# RAM.net
KiCad netlist of a schematic drawn in Altium Designer
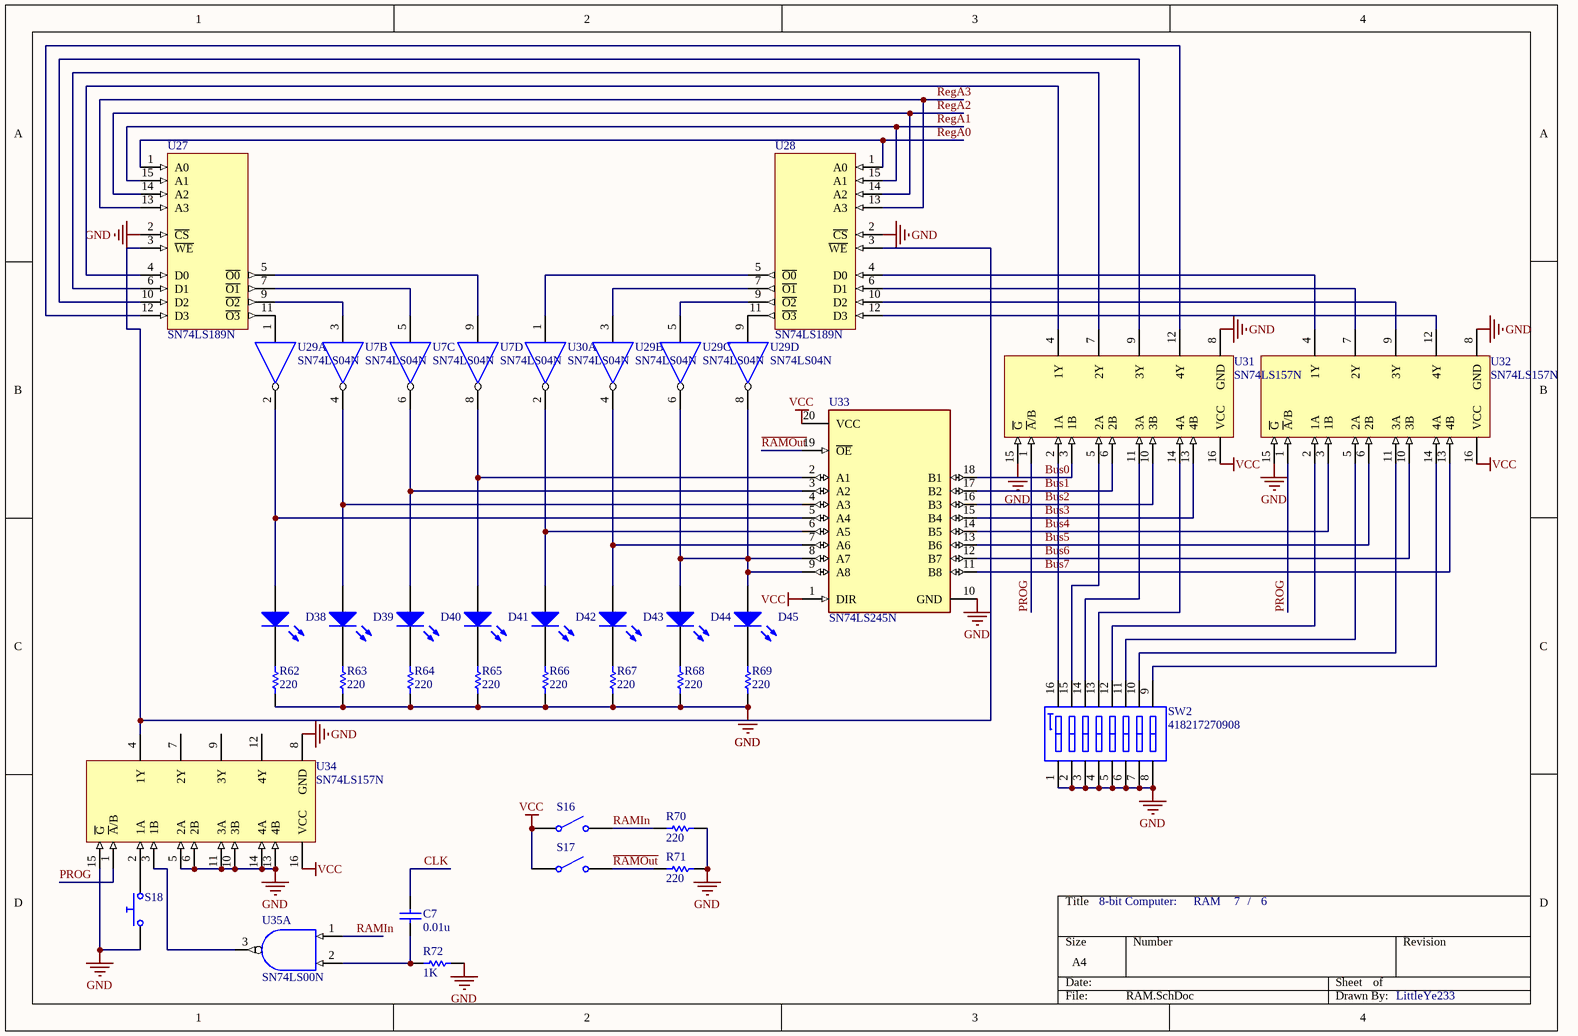
[diagram p0: RAM.SchDoc]

(export (version "E")
  (design (tool "Eeschema 10.0.6"))
  (components
    (comp (ref "C7")
      (value "0.01u")
      (description "Capacitor")
      (libsource (lib "Simulation Generic Components") (part "Capacitor"))
    )
    (comp (ref "D38")
      (value "Light-Emitting Diode")
      (libsource (lib "Simulation Generic Components") (part "LED"))
    )
    (comp (ref "D39")
      (value "Light-Emitting Diode")
      (libsource (lib "Simulation Generic Components") (part "LED"))
    )
    (comp (ref "D40")
      (value "Light-Emitting Diode")
      (libsource (lib "Simulation Generic Components") (part "LED"))
    )
    (comp (ref "D41")
      (value "Light-Emitting Diode")
      (libsource (lib "Simulation Generic Components") (part "LED"))
    )
    (comp (ref "D42")
      (value "Light-Emitting Diode")
      (libsource (lib "Simulation Generic Components") (part "LED"))
    )
    (comp (ref "D43")
      (value "Light-Emitting Diode")
      (libsource (lib "Simulation Generic Components") (part "LED"))
    )
    (comp (ref "D44")
      (value "Light-Emitting Diode")
      (libsource (lib "Simulation Generic Components") (part "LED"))
    )
    (comp (ref "D45")
      (value "Light-Emitting Diode")
      (libsource (lib "Simulation Generic Components") (part "LED"))
    )
    (comp (ref "R62")
      (value "220")
      (description "Resistor")
      (libsource (lib "Simulation Generic Components") (part "Resistor"))
    )
    (comp (ref "R63")
      (value "220")
      (description "Resistor")
      (libsource (lib "Simulation Generic Components") (part "Resistor"))
    )
    (comp (ref "R64")
      (value "220")
      (description "Resistor")
      (libsource (lib "Simulation Generic Components") (part "Resistor"))
    )
    (comp (ref "R65")
      (value "220")
      (description "Resistor")
      (libsource (lib "Simulation Generic Components") (part "Resistor"))
    )
    (comp (ref "R66")
      (value "220")
      (description "Resistor")
      (libsource (lib "Simulation Generic Components") (part "Resistor"))
    )
    (comp (ref "R67")
      (value "220")
      (description "Resistor")
      (libsource (lib "Simulation Generic Components") (part "Resistor"))
    )
    (comp (ref "R68")
      (value "220")
      (description "Resistor")
      (libsource (lib "Simulation Generic Components") (part "Resistor"))
    )
    (comp (ref "R69")
      (value "220")
      (description "Resistor")
      (libsource (lib "Simulation Generic Components") (part "Resistor"))
    )
    (comp (ref "R70")
      (value "220")
      (description "Resistor")
      (libsource (lib "Simulation Generic Components") (part "Resistor"))
    )
    (comp (ref "R71")
      (value "220")
      (description "Resistor")
      (libsource (lib "Simulation Generic Components") (part "Resistor"))
    )
    (comp (ref "R72")
      (value "1K")
      (description "Resistor")
      (libsource (lib "Simulation Generic Components") (part "Resistor"))
    )
    (comp (ref "S16")
      (value "Single-Pole, Single-Throw Switch")
      (libsource (lib "Simulation Generic Components") (part "SPST SW"))
    )
    (comp (ref "S17")
      (value "Single-Pole, Single-Throw Switch")
      (libsource (lib "Simulation Generic Components") (part "SPST SW"))
    )
    (comp (ref "S18")
      (value "Push Button Normally Opened")
      (libsource (lib "Simulation Generic Components") (part "Push Button NO"))
    )
    (comp (ref "SW2")
      (value "418217270908")
      (footprint "418217270908")
      (description "WS-DITU 2.54 mm right angled compact THT Dip Switch with raised actuator")
      (fields (field (name "MANUFACTURER") "Wuerth Elektronik"))
      (libsource (lib "418217270908") (part "CMP-1441-00017-1"))
    )
    (comp (ref "U7")
      (value "SN74LS04N")
      (footprint "N0014A")
      (description "Hex inverters, N0014A, TUBE")
      (fields
        (field (name "MANUFACTURER") "Texas Instruments")
        (field (name "GENERIC PART NUMBER") "SN74LS04")
      )
      (libsource (lib "SN74LS04N") (part "CMP-1615-00911-2"))
    )
    (comp (ref "U27") (value "SN74LS189N") (libsource (lib "SN74LS189N") (part "SN74LS189N")))
    (comp (ref "U28") (value "SN74LS189N") (libsource (lib "") (part "SN74LS189N_1")))
    (comp (ref "U29")
      (value "SN74LS04N")
      (footprint "N0014A")
      (description "Hex inverters, N0014A, TUBE")
      (fields
        (field (name "MANUFACTURER") "Texas Instruments")
        (field (name "GENERIC PART NUMBER") "SN74LS04")
      )
      (libsource (lib "SN74LS04N") (part "CMP-1615-00911-2"))
    )
    (comp (ref "U30")
      (value "SN74LS04N")
      (footprint "N0014A")
      (description "Hex inverters, N0014A, TUBE")
      (fields
        (field (name "MANUFACTURER") "Texas Instruments")
        (field (name "GENERIC PART NUMBER") "SN74LS04")
      )
      (libsource (lib "SN74LS04N") (part "CMP-1615-00911-2"))
    )
    (comp (ref "U31")
      (value "SN74LS157N")
      (footprint "N0016A")
      (description "Quadruple 2-Line To 1-Line Data Selectors/Multiplexers, N0016A, TUBE")
      (fields
        (field (name "MANUFACTURER") "Texas Instruments")
        (field (name "GENERIC PART NUMBER") "SN74LS157")
      )
      (libsource (lib "SN74LS157N") (part "CMP-1633-00683-2"))
    )
    (comp (ref "U32")
      (value "SN74LS157N")
      (footprint "N0016A")
      (description "Quadruple 2-Line To 1-Line Data Selectors/Multiplexers, N0016A, TUBE")
      (fields
        (field (name "MANUFACTURER") "Texas Instruments")
        (field (name "GENERIC PART NUMBER") "SN74LS157")
      )
      (libsource (lib "SN74LS157N") (part "CMP-1633-00683-2"))
    )
    (comp (ref "U33")
      (value "SN74LS245N")
      (footprint "FP-N0020A-MFG")
      (description "IC TXRX NON-INVERT 5.25V 20DIP")
      (libsource (lib "SN74LS245N") (part "CMP-1620-00419-3"))
    )
    (comp (ref "U34")
      (value "SN74LS157N")
      (footprint "N0016A")
      (description "Quadruple 2-Line To 1-Line Data Selectors/Multiplexers, N0016A, TUBE")
      (fields
        (field (name "MANUFACTURER") "Texas Instruments")
        (field (name "GENERIC PART NUMBER") "SN74LS157")
      )
      (libsource (lib "SN74LS157N") (part "CMP-1633-00683-2"))
    )
    (comp (ref "U35")
      (value "SN74LS00N")
      (footprint "N0014A")
      (description "Quad 2-input positive-NAND gates, N0014A, TUBE")
      (fields
        (field (name "MANUFACTURER") "Texas Instruments")
        (field (name "GENERIC PART NUMBER") "SN74LS00")
      )
      (libsource (lib "SN74LS00N") (part "CMP-1627-00476-2"))
    )
  )
  (nets
    (net (code "1") (name "/Bus0") (class "Default")
      (node (ref "U31") (pin "3") (pinfunction "1B_3") (pintype "input"))
      (node (ref "U33") (pin "18") (pinfunction "B1_18") (pintype "bidirectional"))
    )
    (net (code "2") (name "/Bus1") (class "Default")
      (node (ref "U31") (pin "6") (pinfunction "2B_6") (pintype "input"))
      (node (ref "U33") (pin "17") (pinfunction "B2_17") (pintype "bidirectional"))
    )
    (net (code "3") (name "/Bus2") (class "Default")
      (node (ref "U31") (pin "10") (pinfunction "3B_10") (pintype "input"))
      (node (ref "U33") (pin "16") (pinfunction "B3_16") (pintype "bidirectional"))
    )
    (net (code "4") (name "/Bus3") (class "Default")
      (node (ref "U31") (pin "13") (pinfunction "4B_13") (pintype "input"))
      (node (ref "U33") (pin "15") (pinfunction "B4_15") (pintype "bidirectional"))
    )
    (net (code "5") (name "/Bus4") (class "Default")
      (node (ref "U32") (pin "3") (pinfunction "1B_3") (pintype "input"))
      (node (ref "U33") (pin "14") (pinfunction "B5_14") (pintype "bidirectional"))
    )
    (net (code "6") (name "/Bus5") (class "Default")
      (node (ref "U32") (pin "6") (pinfunction "2B_6") (pintype "input"))
      (node (ref "U33") (pin "13") (pinfunction "B6_13") (pintype "bidirectional"))
    )
    (net (code "7") (name "/Bus6") (class "Default")
      (node (ref "U32") (pin "10") (pinfunction "3B_10") (pintype "input"))
      (node (ref "U33") (pin "12") (pinfunction "B7_12") (pintype "bidirectional"))
    )
    (net (code "8") (name "/Bus7") (class "Default")
      (node (ref "U32") (pin "13") (pinfunction "4B_13") (pintype "input"))
      (node (ref "U33") (pin "11") (pinfunction "B8_11") (pintype "bidirectional"))
    )
    (net (code "9") (name "/CLK") (class "Default")
      (node (ref "C7") (pin "2") (pinfunction "2_2") (pintype "passive"))
    )
    (net (code "10") (name "/PROG") (class "Default")
      (node (ref "U31") (pin "1") (pinfunction "~{A}/B_1") (pintype "input"))
      (node (ref "U32") (pin "1") (pinfunction "~{A}/B_1") (pintype "input"))
      (node (ref "U34") (pin "1") (pinfunction "~{A}/B_1") (pintype "input"))
    )
    (net (code "11") (name "/RAMIn") (class "Default")
      (node (ref "R70") (pin "2") (pinfunction "2_2") (pintype "passive"))
      (node (ref "S16") (pin "2") (pinfunction "2_2") (pintype "passive"))
      (node (ref "U35") (pin "1") (pinfunction "1A_1") (pintype "input"))
    )
    (net (code "12") (name "/RegA0") (class "Default")
      (node (ref "U27") (pin "1") (pinfunction "A0_1") (pintype "input"))
      (node (ref "U28") (pin "1") (pinfunction "A0_1") (pintype "input"))
    )
    (net (code "13") (name "/RegA1") (class "Default")
      (node (ref "U27") (pin "15") (pinfunction "A1_15") (pintype "input"))
      (node (ref "U28") (pin "15") (pinfunction "A1_15") (pintype "input"))
    )
    (net (code "14") (name "/RegA2") (class "Default")
      (node (ref "U27") (pin "14") (pinfunction "A2_14") (pintype "input"))
      (node (ref "U28") (pin "14") (pinfunction "A2_14") (pintype "input"))
    )
    (net (code "15") (name "/RegA3") (class "Default")
      (node (ref "U27") (pin "13") (pinfunction "A3_13") (pintype "input"))
      (node (ref "U28") (pin "13") (pinfunction "A3_13") (pintype "input"))
    )
    (net (code "16") (name "/~{RAMOut}") (class "Default")
      (node (ref "R71") (pin "2") (pinfunction "2_2") (pintype "passive"))
      (node (ref "S17") (pin "2") (pinfunction "2_2") (pintype "passive"))
      (node (ref "U33") (pin "19") (pinfunction "~{OE}_19") (pintype "input"))
    )
    (net (code "17") (name "GND") (class "Default")
      (node (ref "R62") (pin "1") (pinfunction "1_1") (pintype "passive"))
      (node (ref "R63") (pin "1") (pinfunction "1_1") (pintype "passive"))
      (node (ref "R64") (pin "1") (pinfunction "1_1") (pintype "passive"))
      (node (ref "R65") (pin "1") (pinfunction "1_1") (pintype "passive"))
      (node (ref "R66") (pin "1") (pinfunction "1_1") (pintype "passive"))
      (node (ref "R67") (pin "1") (pinfunction "1_1") (pintype "passive"))
      (node (ref "R68") (pin "1") (pinfunction "1_1") (pintype "passive"))
      (node (ref "R69") (pin "1") (pinfunction "1_1") (pintype "passive"))
      (node (ref "R70") (pin "1") (pinfunction "1_1") (pintype "passive"))
      (node (ref "R71") (pin "1") (pinfunction "1_1") (pintype "passive"))
      (node (ref "R72") (pin "2") (pinfunction "2_2") (pintype "passive"))
      (node (ref "S18") (pin "1") (pinfunction "1_1") (pintype "passive"))
      (node (ref "SW2") (pin "1") (pinfunction "1_1") (pintype "passive"))
      (node (ref "SW2") (pin "2") (pinfunction "2_2") (pintype "passive"))
      (node (ref "SW2") (pin "3") (pinfunction "3_3") (pintype "passive"))
      (node (ref "SW2") (pin "4") (pinfunction "4_4") (pintype "passive"))
      (node (ref "SW2") (pin "5") (pinfunction "5_5") (pintype "passive"))
      (node (ref "SW2") (pin "6") (pinfunction "6_6") (pintype "passive"))
      (node (ref "SW2") (pin "7") (pinfunction "7_7") (pintype "passive"))
      (node (ref "SW2") (pin "8") (pinfunction "8_8") (pintype "passive"))
      (node (ref "U27") (pin "2") (pinfunction "~{CS}_2") (pintype "input"))
      (node (ref "U28") (pin "2") (pinfunction "~{CS}_2") (pintype "input"))
      (node (ref "U31") (pin "15") (pinfunction "~{G}_15") (pintype "input"))
      (node (ref "U31") (pin "8") (pinfunction "GND_8") (pintype "power_in"))
      (node (ref "U32") (pin "15") (pinfunction "~{G}_15") (pintype "input"))
      (node (ref "U32") (pin "8") (pinfunction "GND_8") (pintype "power_in"))
      (node (ref "U33") (pin "10") (pinfunction "GND_10") (pintype "power_in"))
      (node (ref "U34") (pin "10") (pinfunction "3B_10") (pintype "input"))
      (node (ref "U34") (pin "11") (pinfunction "3A_11") (pintype "input"))
      (node (ref "U34") (pin "13") (pinfunction "4B_13") (pintype "input"))
      (node (ref "U34") (pin "14") (pinfunction "4A_14") (pintype "input"))
      (node (ref "U34") (pin "15") (pinfunction "~{G}_15") (pintype "input"))
      (node (ref "U34") (pin "5") (pinfunction "2A_5") (pintype "input"))
      (node (ref "U34") (pin "6") (pinfunction "2B_6") (pintype "input"))
      (node (ref "U34") (pin "8") (pinfunction "GND_8") (pintype "power_in"))
    )
    (net (code "18") (name "Net-(D38-A)") (class "Default")
      (node (ref "D38") (pin "1") (pinfunction "A_1") (pintype "passive"))
      (node (ref "U29") (pin "2") (pinfunction "~{1Y}_2") (pintype "passive"))
      (node (ref "U33") (pin "5") (pinfunction "A4_5") (pintype "bidirectional"))
    )
    (net (code "19") (name "Net-(D38-K)") (class "Default")
      (node (ref "D38") (pin "2") (pinfunction "K_2") (pintype "passive"))
      (node (ref "R62") (pin "2") (pinfunction "2_2") (pintype "passive"))
    )
    (net (code "20") (name "Net-(D39-A)") (class "Default")
      (node (ref "D39") (pin "1") (pinfunction "A_1") (pintype "passive"))
      (node (ref "U33") (pin "4") (pinfunction "A3_4") (pintype "bidirectional"))
      (node (ref "U7") (pin "4") (pinfunction "~{2Y}_4") (pintype "passive"))
    )
    (net (code "21") (name "Net-(D39-K)") (class "Default")
      (node (ref "D39") (pin "2") (pinfunction "K_2") (pintype "passive"))
      (node (ref "R63") (pin "2") (pinfunction "2_2") (pintype "passive"))
    )
    (net (code "22") (name "Net-(D40-A)") (class "Default")
      (node (ref "D40") (pin "1") (pinfunction "A_1") (pintype "passive"))
      (node (ref "U33") (pin "3") (pinfunction "A2_3") (pintype "bidirectional"))
      (node (ref "U7") (pin "6") (pinfunction "~{3Y}_6") (pintype "passive"))
    )
    (net (code "23") (name "Net-(D40-K)") (class "Default")
      (node (ref "D40") (pin "2") (pinfunction "K_2") (pintype "passive"))
      (node (ref "R64") (pin "2") (pinfunction "2_2") (pintype "passive"))
    )
    (net (code "24") (name "Net-(D41-A)") (class "Default")
      (node (ref "D41") (pin "1") (pinfunction "A_1") (pintype "passive"))
      (node (ref "U33") (pin "2") (pinfunction "A1_2") (pintype "bidirectional"))
      (node (ref "U7") (pin "8") (pinfunction "~{4Y}_8") (pintype "passive"))
    )
    (net (code "25") (name "Net-(D41-K)") (class "Default")
      (node (ref "D41") (pin "2") (pinfunction "K_2") (pintype "passive"))
      (node (ref "R65") (pin "2") (pinfunction "2_2") (pintype "passive"))
    )
    (net (code "26") (name "Net-(D42-A)") (class "Default")
      (node (ref "D42") (pin "1") (pinfunction "A_1") (pintype "passive"))
      (node (ref "U30") (pin "2") (pinfunction "~{1Y}_2") (pintype "passive"))
      (node (ref "U33") (pin "6") (pinfunction "A5_6") (pintype "bidirectional"))
    )
    (net (code "27") (name "Net-(D42-K)") (class "Default")
      (node (ref "D42") (pin "2") (pinfunction "K_2") (pintype "passive"))
      (node (ref "R66") (pin "2") (pinfunction "2_2") (pintype "passive"))
    )
    (net (code "28") (name "Net-(D43-A)") (class "Default")
      (node (ref "D43") (pin "1") (pinfunction "A_1") (pintype "passive"))
      (node (ref "U29") (pin "4") (pinfunction "~{2Y}_4") (pintype "passive"))
      (node (ref "U33") (pin "7") (pinfunction "A6_7") (pintype "bidirectional"))
    )
    (net (code "29") (name "Net-(D43-K)") (class "Default")
      (node (ref "D43") (pin "2") (pinfunction "K_2") (pintype "passive"))
      (node (ref "R67") (pin "2") (pinfunction "2_2") (pintype "passive"))
    )
    (net (code "30") (name "Net-(D44-A)") (class "Default")
      (node (ref "D44") (pin "1") (pinfunction "A_1") (pintype "passive"))
      (node (ref "D45") (pin "1") (pinfunction "A_1") (pintype "passive"))
      (node (ref "U29") (pin "6") (pinfunction "~{3Y}_6") (pintype "passive"))
      (node (ref "U29") (pin "8") (pinfunction "~{4Y}_8") (pintype "passive"))
      (node (ref "U33") (pin "8") (pinfunction "A7_8") (pintype "bidirectional"))
      (node (ref "U33") (pin "9") (pinfunction "A8_9") (pintype "bidirectional"))
    )
    (net (code "31") (name "Net-(D44-K)") (class "Default")
      (node (ref "D44") (pin "2") (pinfunction "K_2") (pintype "passive"))
      (node (ref "R68") (pin "2") (pinfunction "2_2") (pintype "passive"))
    )
    (net (code "32") (name "Net-(D45-K)") (class "Default")
      (node (ref "D45") (pin "2") (pinfunction "K_2") (pintype "passive"))
      (node (ref "R69") (pin "2") (pinfunction "2_2") (pintype "passive"))
    )
    (net (code "33") (name "Net-(U27-D0)") (class "Default")
      (node (ref "U27") (pin "4") (pinfunction "D0_4") (pintype "input"))
      (node (ref "U31") (pin "4") (pinfunction "1Y_4") (pintype "passive"))
    )
    (net (code "34") (name "Net-(U27-D1)") (class "Default")
      (node (ref "U27") (pin "6") (pinfunction "D1_6") (pintype "input"))
      (node (ref "U31") (pin "7") (pinfunction "2Y_7") (pintype "passive"))
    )
    (net (code "35") (name "Net-(U27-D2)") (class "Default")
      (node (ref "U27") (pin "10") (pinfunction "D2_10") (pintype "input"))
      (node (ref "U31") (pin "9") (pinfunction "3Y_9") (pintype "passive"))
    )
    (net (code "36") (name "Net-(U27-D3)") (class "Default")
      (node (ref "U27") (pin "12") (pinfunction "D3_12") (pintype "input"))
      (node (ref "U31") (pin "12") (pinfunction "4Y_12") (pintype "passive"))
    )
    (net (code "37") (name "Net-(U27-~{O0})") (class "Default")
      (node (ref "U27") (pin "5") (pinfunction "~{O0}_5") (pintype "output"))
      (node (ref "U7") (pin "9") (pinfunction "4A_9") (pintype "passive"))
    )
    (net (code "38") (name "Net-(U27-~{O1})") (class "Default")
      (node (ref "U27") (pin "7") (pinfunction "~{O1}_7") (pintype "output"))
      (node (ref "U7") (pin "5") (pinfunction "3A_5") (pintype "passive"))
    )
    (net (code "39") (name "Net-(U27-~{O2})") (class "Default")
      (node (ref "U27") (pin "9") (pinfunction "~{O2}_9") (pintype "output"))
      (node (ref "U7") (pin "3") (pinfunction "2A_3") (pintype "passive"))
    )
    (net (code "40") (name "Net-(U27-~{O3})") (class "Default")
      (node (ref "U27") (pin "11") (pinfunction "~{O3}_11") (pintype "output"))
      (node (ref "U29") (pin "1") (pinfunction "1A_1") (pintype "passive"))
    )
    (net (code "41") (name "Net-(U27-~{WE})") (class "Default")
      (node (ref "U27") (pin "3") (pinfunction "~{WE}_3") (pintype "input"))
      (node (ref "U28") (pin "3") (pinfunction "~{WE}_3") (pintype "input"))
      (node (ref "U34") (pin "4") (pinfunction "1Y_4") (pintype "passive"))
    )
    (net (code "42") (name "Net-(U28-D0)") (class "Default")
      (node (ref "U28") (pin "4") (pinfunction "D0_4") (pintype "input"))
      (node (ref "U32") (pin "4") (pinfunction "1Y_4") (pintype "passive"))
    )
    (net (code "43") (name "Net-(U28-D1)") (class "Default")
      (node (ref "U28") (pin "6") (pinfunction "D1_6") (pintype "input"))
      (node (ref "U32") (pin "7") (pinfunction "2Y_7") (pintype "passive"))
    )
    (net (code "44") (name "Net-(U28-D2)") (class "Default")
      (node (ref "U28") (pin "10") (pinfunction "D2_10") (pintype "input"))
      (node (ref "U32") (pin "9") (pinfunction "3Y_9") (pintype "passive"))
    )
    (net (code "45") (name "Net-(U28-D3)") (class "Default")
      (node (ref "U28") (pin "12") (pinfunction "D3_12") (pintype "input"))
      (node (ref "U32") (pin "12") (pinfunction "4Y_12") (pintype "passive"))
    )
    (net (code "46") (name "Net-(U28-~{O0})") (class "Default")
      (node (ref "U28") (pin "5") (pinfunction "~{O0}_5") (pintype "output"))
      (node (ref "U30") (pin "1") (pinfunction "1A_1") (pintype "passive"))
    )
    (net (code "47") (name "Net-(U28-~{O1})") (class "Default")
      (node (ref "U28") (pin "7") (pinfunction "~{O1}_7") (pintype "output"))
      (node (ref "U29") (pin "3") (pinfunction "2A_3") (pintype "passive"))
    )
    (net (code "48") (name "Net-(U28-~{O2})") (class "Default")
      (node (ref "U28") (pin "9") (pinfunction "~{O2}_9") (pintype "output"))
      (node (ref "U29") (pin "5") (pinfunction "3A_5") (pintype "passive"))
    )
    (net (code "49") (name "Net-(U28-~{O3})") (class "Default")
      (node (ref "U28") (pin "11") (pinfunction "~{O3}_11") (pintype "output"))
      (node (ref "U29") (pin "9") (pinfunction "4A_9") (pintype "passive"))
    )
    (net (code "50") (name "Net-(U31-1A)") (class "Default")
      (node (ref "SW2") (pin "16") (pinfunction "16_16") (pintype "passive"))
      (node (ref "U31") (pin "2") (pinfunction "1A_2") (pintype "input"))
    )
    (net (code "51") (name "Net-(U31-2A)") (class "Default")
      (node (ref "SW2") (pin "15") (pinfunction "15_15") (pintype "passive"))
      (node (ref "U31") (pin "5") (pinfunction "2A_5") (pintype "input"))
    )
    (net (code "52") (name "Net-(U31-3A)") (class "Default")
      (node (ref "SW2") (pin "14") (pinfunction "14_14") (pintype "passive"))
      (node (ref "U31") (pin "11") (pinfunction "3A_11") (pintype "input"))
    )
    (net (code "53") (name "Net-(U31-4A)") (class "Default")
      (node (ref "SW2") (pin "13") (pinfunction "13_13") (pintype "passive"))
      (node (ref "U31") (pin "14") (pinfunction "4A_14") (pintype "input"))
    )
    (net (code "54") (name "Net-(U32-1A)") (class "Default")
      (node (ref "SW2") (pin "12") (pinfunction "12_12") (pintype "passive"))
      (node (ref "U32") (pin "2") (pinfunction "1A_2") (pintype "input"))
    )
    (net (code "55") (name "Net-(U32-2A)") (class "Default")
      (node (ref "SW2") (pin "11") (pinfunction "11_11") (pintype "passive"))
      (node (ref "U32") (pin "5") (pinfunction "2A_5") (pintype "input"))
    )
    (net (code "56") (name "Net-(U32-3A)") (class "Default")
      (node (ref "SW2") (pin "10") (pinfunction "10_10") (pintype "passive"))
      (node (ref "U32") (pin "11") (pinfunction "3A_11") (pintype "input"))
    )
    (net (code "57") (name "Net-(U32-4A)") (class "Default")
      (node (ref "SW2") (pin "9") (pinfunction "9_9") (pintype "passive"))
      (node (ref "U32") (pin "14") (pinfunction "4A_14") (pintype "input"))
    )
    (net (code "58") (name "Net-(U34-1A)") (class "Default")
      (node (ref "S18") (pin "2") (pinfunction "2_2") (pintype "passive"))
      (node (ref "U34") (pin "2") (pinfunction "1A_2") (pintype "input"))
    )
    (net (code "59") (name "Net-(U34-1B)") (class "Default")
      (node (ref "U34") (pin "3") (pinfunction "1B_3") (pintype "input"))
      (node (ref "U35") (pin "3") (pinfunction "1Y_3") (pintype "output"))
    )
    (net (code "60") (name "Net-(U35A-1B)") (class "Default")
      (node (ref "C7") (pin "1") (pinfunction "1_1") (pintype "passive"))
      (node (ref "R72") (pin "1") (pinfunction "1_1") (pintype "passive"))
      (node (ref "U35") (pin "2") (pinfunction "1B_2") (pintype "input"))
    )
    (net (code "61") (name "VCC") (class "Default")
      (node (ref "S16") (pin "1") (pinfunction "1_1") (pintype "passive"))
      (node (ref "S17") (pin "1") (pinfunction "1_1") (pintype "passive"))
      (node (ref "U31") (pin "16") (pinfunction "VCC_16") (pintype "power_in"))
      (node (ref "U32") (pin "16") (pinfunction "VCC_16") (pintype "power_in"))
      (node (ref "U33") (pin "1") (pinfunction "DIR_1") (pintype "input"))
      (node (ref "U33") (pin "20") (pinfunction "VCC_20") (pintype "power_in"))
      (node (ref "U34") (pin "16") (pinfunction "VCC_16") (pintype "power_in"))
    )
    (net (code "62") (name "unconnected-(U34-2Y-Pad7)") (class "Default")
      (node (ref "U34") (pin "7") (pinfunction "2Y_7") (pintype "passive"))
    )
    (net (code "63") (name "unconnected-(U34-3Y-Pad9)") (class "Default")
      (node (ref "U34") (pin "9") (pinfunction "3Y_9") (pintype "passive"))
    )
    (net (code "64") (name "unconnected-(U34-4Y-Pad12)") (class "Default")
      (node (ref "U34") (pin "12") (pinfunction "4Y_12") (pintype "passive"))
    )
  )
)
